# main_board128.net
KiCad netlist of a schematic drawn in EAGLE
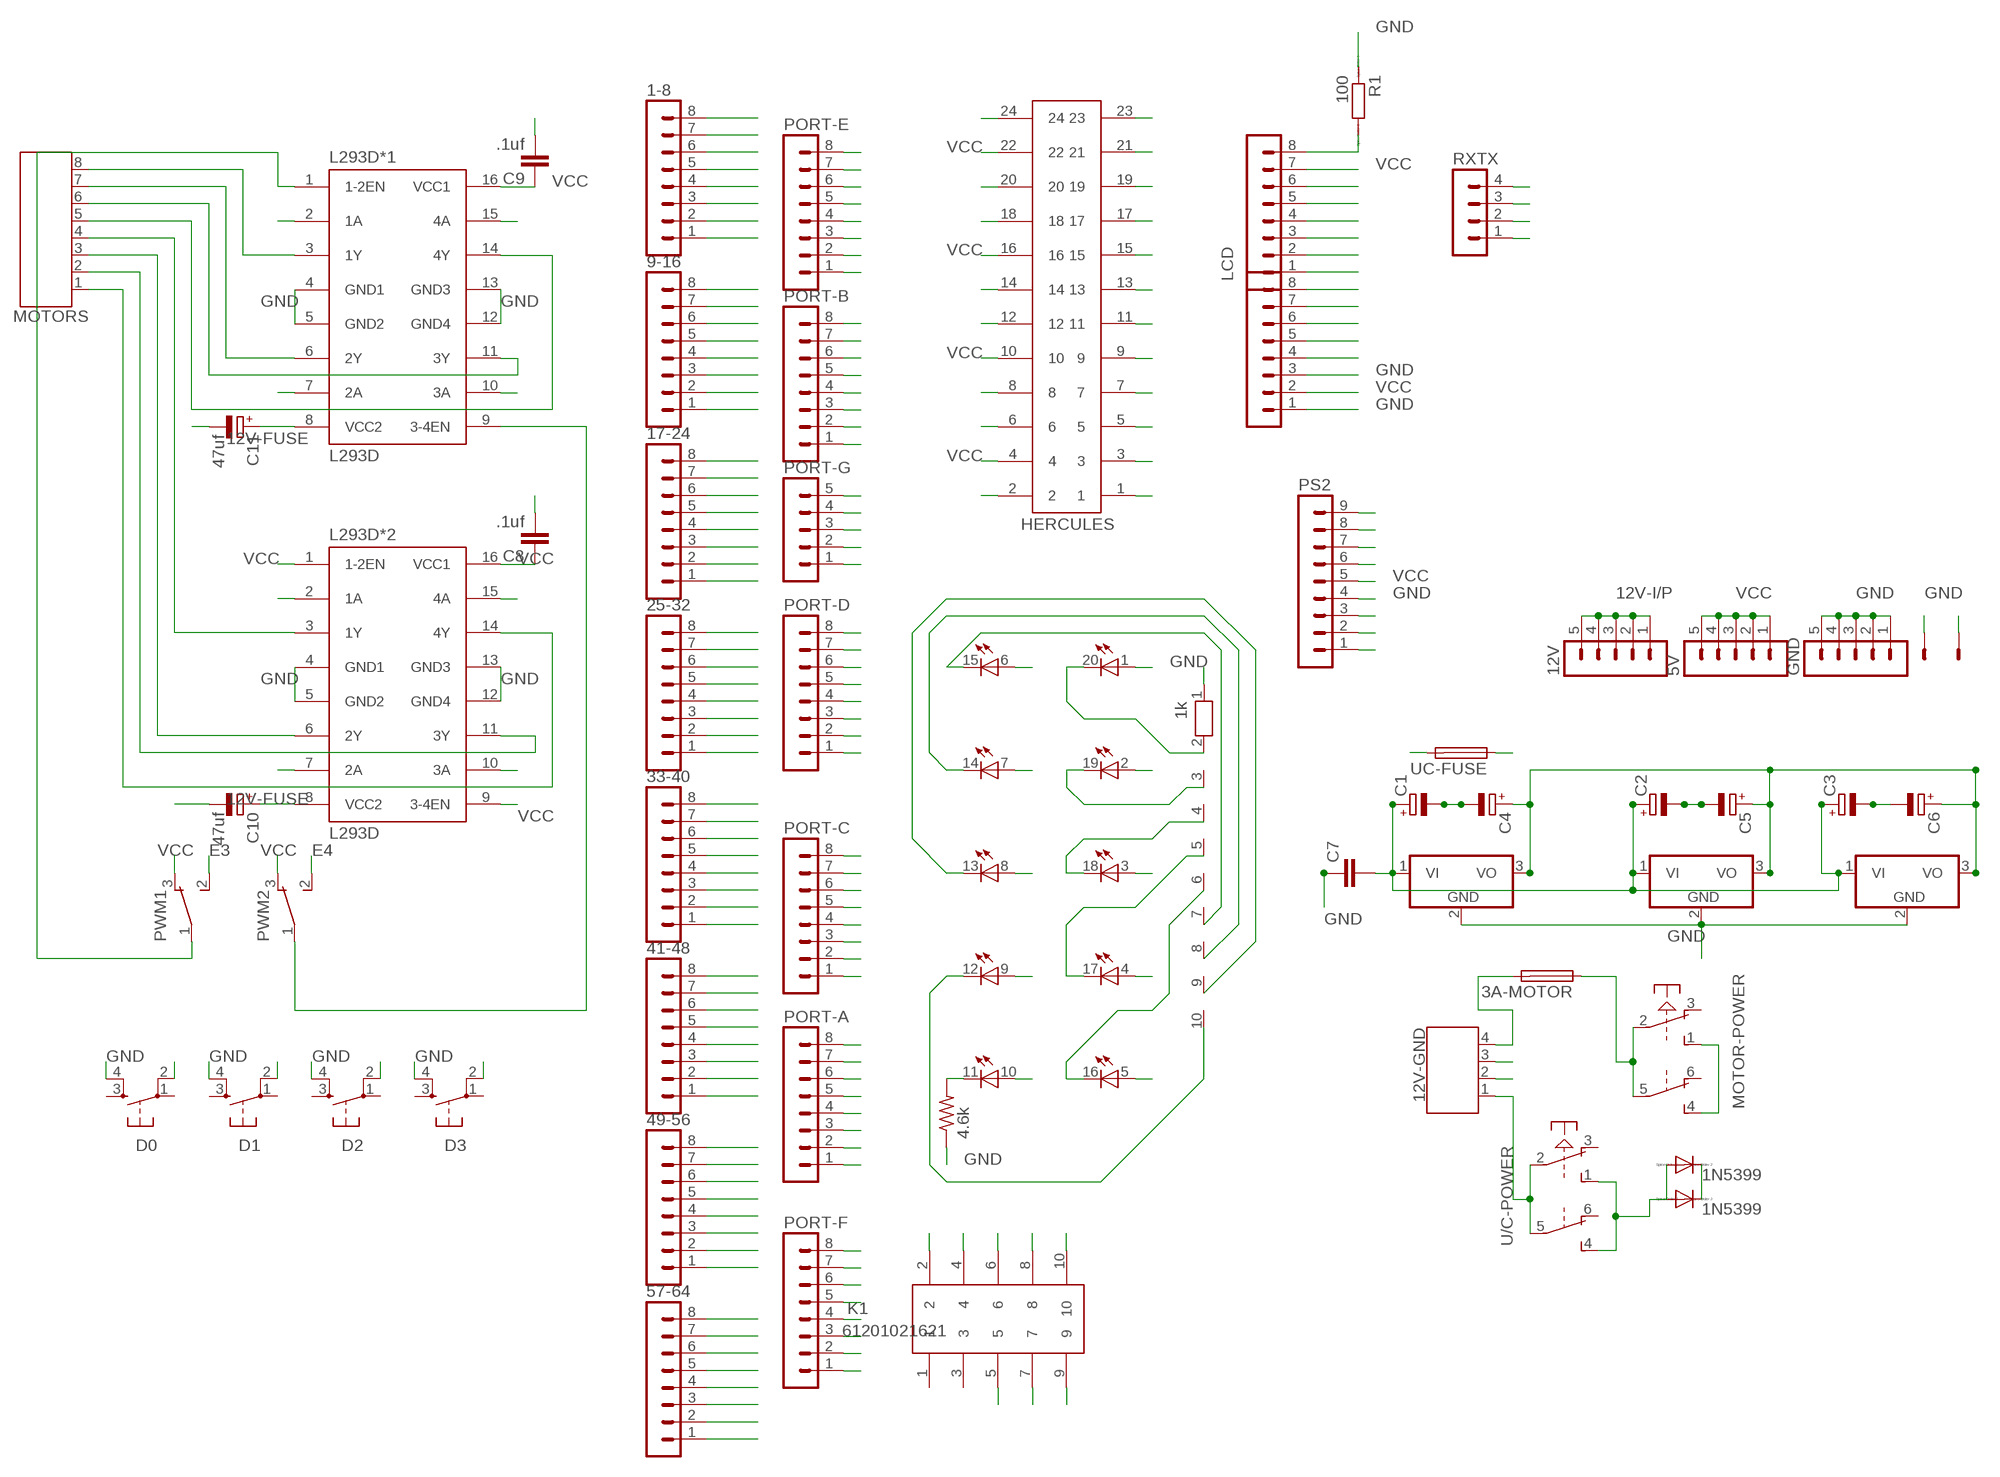
[diagram p0: schematic, sheet 1]

(export (version "E")
  (design (tool "Eeschema 10.0.6"))
  (components
    (comp (ref "1-8")
      (value "MA08-1")
      (footprint "eagle-import:MA08-1")
      (libsource (lib "eagle-import") (part "MA08-1"))
    )
    (comp (ref "3A-MOTOR")
      (value "SH25")
      (footprint "eagle-import:SH25")
      (fields (field (name "MF") "SCHURTER") (field (name "MPN") "0031.8211"))
      (libsource (lib "eagle-import") (part "SH25"))
    )
    (comp (ref "5V")
      (value "MA05-1")
      (footprint "eagle-import:MA05-1")
      (libsource (lib "eagle-import") (part "MA05-1"))
    )
    (comp (ref "9-16")
      (value "MA08-1")
      (footprint "eagle-import:MA08-1")
      (libsource (lib "eagle-import") (part "MA08-1"))
    )
    (comp (ref "12V")
      (value "MA05-1")
      (footprint "eagle-import:MA05-1")
      (libsource (lib "eagle-import") (part "MA05-1"))
    )
    (comp (ref "12V-GND")
      (value "691131710004")
      (footprint "eagle-import:691131710004")
      (libsource (lib "eagle-import") (part "691131710004"))
    )
    (comp (ref "17-24")
      (value "MA08-1")
      (footprint "eagle-import:MA08-1")
      (libsource (lib "eagle-import") (part "MA08-1"))
    )
    (comp (ref "25-32")
      (value "MA08-1")
      (footprint "eagle-import:MA08-1")
      (libsource (lib "eagle-import") (part "MA08-1"))
    )
    (comp (ref "33-40")
      (value "MA08-1")
      (footprint "eagle-import:MA08-1")
      (libsource (lib "eagle-import") (part "MA08-1"))
    )
    (comp (ref "41-48")
      (value "MA08-1")
      (footprint "eagle-import:MA08-1")
      (libsource (lib "eagle-import") (part "MA08-1"))
    )
    (comp (ref "49-56")
      (value "MA08-1")
      (footprint "eagle-import:MA08-1")
      (libsource (lib "eagle-import") (part "MA08-1"))
    )
    (comp (ref "57-64")
      (value "MA08-1")
      (footprint "eagle-import:MA08-1")
      (libsource (lib "eagle-import") (part "MA08-1"))
    )
    (comp (ref "7805-1")
      (value "7805T")
      (footprint "eagle-import:TO220H")
      (libsource (lib "eagle-import") (part "78T05"))
    )
    (comp (ref "7805-2")
      (value "7805T")
      (footprint "eagle-import:TO220H")
      (libsource (lib "eagle-import") (part "78T05"))
    )
    (comp (ref "7805-3")
      (value "7805T")
      (footprint "eagle-import:TO220H")
      (libsource (lib "eagle-import") (part "78T05"))
    )
    (comp (ref "BASEMOTORSLED")
      (value "LB10")
      (footprint "eagle-import:LB10")
      (libsource (lib "eagle-import") (part "LB10"))
    )
    (comp (ref "C1")
      (value "CPOL-EUE2.5-5")
      (footprint "eagle-import:E2,5-5")
      (libsource (lib "eagle-import") (part "CPOL-EUE2.5-5"))
    )
    (comp (ref "C2")
      (value "CPOL-EUE2.5-5")
      (footprint "eagle-import:E2,5-5")
      (libsource (lib "eagle-import") (part "CPOL-EUE2.5-5"))
    )
    (comp (ref "C3")
      (value "CPOL-EUE2.5-5")
      (footprint "eagle-import:E2,5-5")
      (libsource (lib "eagle-import") (part "CPOL-EUE2.5-5"))
    )
    (comp (ref "C4")
      (value "CPOL-EUE2.5-5")
      (footprint "eagle-import:E2,5-5")
      (libsource (lib "eagle-import") (part "CPOL-EUE2.5-5"))
    )
    (comp (ref "C5")
      (value "CPOL-EUE2.5-5")
      (footprint "eagle-import:E2,5-5")
      (libsource (lib "eagle-import") (part "CPOL-EUE2.5-5"))
    )
    (comp (ref "C6")
      (value "CPOL-EUE2.5-5")
      (footprint "eagle-import:E2,5-5")
      (libsource (lib "eagle-import") (part "CPOL-EUE2.5-5"))
    )
    (comp (ref "C7")
      (value "C5/2.5")
      (footprint "eagle-import:C5B2.5")
      (libsource (lib "eagle-import") (part "C5/2.5"))
    )
    (comp (ref "C8")
      (value ".1uf")
      (footprint "eagle-import:C5B2.5")
      (libsource (lib "eagle-import") (part "C5/2.5"))
    )
    (comp (ref "C9")
      (value ".1uf")
      (footprint "eagle-import:C5B2.5")
      (libsource (lib "eagle-import") (part "C5/2.5"))
    )
    (comp (ref "C10")
      (value "47uf")
      (footprint "eagle-import:E2,5-5")
      (libsource (lib "eagle-import") (part "CPOL-EUE2.5-5"))
    )
    (comp (ref "C11")
      (value "47uf")
      (footprint "eagle-import:E2,5-5")
      (libsource (lib "eagle-import") (part "CPOL-EUE2.5-5"))
    )
    (comp (ref "D0")
      (value "DTS-6")
      (footprint "eagle-import:DTS-6")
      (libsource (lib "eagle-import") (part "DTS-6"))
    )
    (comp (ref "D1")
      (value "DTS-6")
      (footprint "eagle-import:DTS-6")
      (libsource (lib "eagle-import") (part "DTS-6"))
    )
    (comp (ref "D2")
      (value "DTS-6")
      (footprint "eagle-import:DTS-6")
      (libsource (lib "eagle-import") (part "DTS-6"))
    )
    (comp (ref "D3")
      (value "DTS-6")
      (footprint "eagle-import:DTS-6")
      (libsource (lib "eagle-import") (part "DTS-6"))
    )
    (comp (ref "GND")
      (value "MA05-1")
      (footprint "eagle-import:MA05-1")
      (libsource (lib "eagle-import") (part "MA05-1"))
    )
    (comp (ref "HERCULES")
      (value "61202421621")
      (footprint "eagle-import:61202421621")
      (libsource (lib "eagle-import") (part "61202421621"))
    )
    (comp (ref "K1")
      (value "61201021621")
      (footprint "eagle-import:61201021621")
      (libsource (lib "eagle-import") (part "61201021621"))
    )
    (comp (ref "L293D*1")
      (value "L293D")
      (footprint "eagle-import:DIL16")
      (libsource (lib "eagle-import") (part "L293D"))
    )
    (comp (ref "L293D*2")
      (value "L293D")
      (footprint "eagle-import:DIL16")
      (libsource (lib "eagle-import") (part "L293D"))
    )
    (comp (ref "LCD")
      (value "MA08-1")
      (footprint "eagle-import:MA08-1")
      (libsource (lib "eagle-import") (part "MA08-1"))
    )
    (comp (ref "LCD*")
      (value "MA08-1")
      (footprint "eagle-import:MA08-1")
      (libsource (lib "eagle-import") (part "MA08-1"))
    )
    (comp (ref "MOTOR-POWER")
      (value "PVA2R")
      (footprint "eagle-import:PVA2R")
      (libsource (lib "eagle-import") (part "PVA2R"))
    )
    (comp (ref "MOTORS")
      (value "691131710008")
      (footprint "eagle-import:691131710008")
      (libsource (lib "eagle-import") (part "691131710008"))
    )
    (comp (ref "PORT-A")
      (value "MA08-1")
      (footprint "eagle-import:MA08-1")
      (libsource (lib "eagle-import") (part "MA08-1"))
    )
    (comp (ref "PORT-B")
      (value "MA08-1")
      (footprint "eagle-import:MA08-1")
      (libsource (lib "eagle-import") (part "MA08-1"))
    )
    (comp (ref "PORT-C")
      (value "MA08-1")
      (footprint "eagle-import:MA08-1")
      (libsource (lib "eagle-import") (part "MA08-1"))
    )
    (comp (ref "PORT-D")
      (value "MA08-1")
      (footprint "eagle-import:MA08-1")
      (libsource (lib "eagle-import") (part "MA08-1"))
    )
    (comp (ref "PORT-E")
      (value "MA08-1")
      (footprint "eagle-import:MA08-1")
      (libsource (lib "eagle-import") (part "MA08-1"))
    )
    (comp (ref "PORT-F")
      (value "MA08-1")
      (footprint "eagle-import:MA08-1")
      (libsource (lib "eagle-import") (part "MA08-1"))
    )
    (comp (ref "PORT-G")
      (value "MA05-1")
      (footprint "eagle-import:MA05-1")
      (libsource (lib "eagle-import") (part "MA05-1"))
    )
    (comp (ref "POWER-D1")
      (value "1N5399")
      (footprint "eagle-import:DO15-12")
      (libsource (lib "eagle-import") (part "1N5060GP"))
    )
    (comp (ref "POWER-D2")
      (value "1N5399")
      (footprint "eagle-import:DO15-12")
      (libsource (lib "eagle-import") (part "1N5060GP"))
    )
    (comp (ref "PS2")
      (value "MA09-1")
      (footprint "eagle-import:MA09-1")
      (libsource (lib "eagle-import") (part "MA09-1"))
    )
    (comp (ref "PWM1")
      (value "450301014042")
      (footprint "eagle-import:450301014042")
      (libsource (lib "eagle-import") (part "450301014042"))
    )
    (comp (ref "PWM2")
      (value "450301014042")
      (footprint "eagle-import:450301014042")
      (libsource (lib "eagle-import") (part "450301014042"))
    )
    (comp (ref "R1")
      (value "100")
      (footprint "eagle-import:0204_7")
      (libsource (lib "eagle-import") (part "R0204/7"))
    )
    (comp (ref "R2")
      (value "4.6k")
      (footprint "eagle-import:0204_5")
      (libsource (lib "eagle-import") (part "R-US_0204/5"))
    )
    (comp (ref "RN1")
      (value "1k")
      (footprint "eagle-import:RN-10")
      (libsource (lib "eagle-import") (part "RN09"))
    )
    (comp (ref "RXTX")
      (value "MA04-1")
      (footprint "eagle-import:MA04-1")
      (libsource (lib "eagle-import") (part "MA04-1"))
    )
    (comp (ref "SENSOR-POWER")
      (value "KK-156-2")
      (footprint "eagle-import:KK-156-2")
      (libsource (lib "eagle-import") (part "KK-156-2"))
    )
    (comp (ref "U/C-POWER")
      (value "PVA2R")
      (footprint "eagle-import:PVA2R")
      (libsource (lib "eagle-import") (part "PVA2R"))
    )
    (comp (ref "UC-FUSE")
      (value "SH25")
      (footprint "eagle-import:SH25")
      (fields (field (name "MF") "SCHURTER") (field (name "MPN") "0031.8211"))
      (libsource (lib "eagle-import") (part "SH25"))
    )
  )
  (nets
    (net (code "1") (name "/12V") (class "Default")
      (node (ref "7805-1") (pin "1") (pinfunction "VI_1") (pintype "input"))
      (node (ref "7805-2") (pin "1") (pinfunction "VI_1") (pintype "input"))
      (node (ref "7805-3") (pin "1") (pinfunction "VI_1") (pintype "input"))
      (node (ref "BASEMOTORSLED") (pin "10") (pinfunction "A_10") (pintype "passive"))
      (node (ref "C1") (pin "+") (pinfunction "+_+") (pintype "passive"))
      (node (ref "C2") (pin "+") (pinfunction "+_+") (pintype "passive"))
      (node (ref "C3") (pin "+") (pinfunction "+_+") (pintype "passive"))
      (node (ref "C7") (pin "2") (pinfunction "2_2") (pintype "passive"))
      (node (ref "POWER-D1") (pin "C") (pinfunction "C_C") (pintype "passive"))
      (node (ref "POWER-D2") (pin "C") (pinfunction "C_C") (pintype "passive"))
    )
    (net (code "2") (name "/12V-FUSE") (class "Default")
      (node (ref "C10") (pin "+") (pinfunction "+_+") (pintype "passive"))
      (node (ref "C11") (pin "+") (pinfunction "+_+") (pintype "passive"))
      (node (ref "L293D*1") (pin "8") (pinfunction "VCC2_8") (pintype "power_in"))
      (node (ref "L293D*2") (pin "8") (pinfunction "VCC2_8") (pintype "power_in"))
      (node (ref "MOTOR-POWER") (pin "1") (pinfunction "S_1") (pintype "passive"))
      (node (ref "MOTOR-POWER") (pin "4") (pinfunction "S_4") (pintype "passive"))
    )
    (net (code "3") (name "/12V-I{slash}P") (class "Default")
      (node (ref "12V") (pin "1") (pinfunction "1_1") (pintype "passive"))
      (node (ref "12V") (pin "2") (pinfunction "2_2") (pintype "passive"))
      (node (ref "12V") (pin "3") (pinfunction "3_3") (pintype "passive"))
      (node (ref "12V") (pin "4") (pinfunction "4_4") (pintype "passive"))
      (node (ref "12V") (pin "5") (pinfunction "5_5") (pintype "passive"))
      (node (ref "12V-GND") (pin "1") (pinfunction "1_1") (pintype "passive"))
      (node (ref "12V-GND") (pin "4") (pinfunction "4_4") (pintype "passive"))
      (node (ref "3A-MOTOR") (pin "2") (pinfunction "2_2") (pintype "passive"))
      (node (ref "U/C-POWER") (pin "2") (pinfunction "P_2") (pintype "passive"))
      (node (ref "U/C-POWER") (pin "5") (pinfunction "P_5") (pintype "passive"))
    )
    (net (code "4") (name "/A0") (class "Default")
      (node (ref "49-56") (pin "3") (pinfunction "3_3") (pintype "passive"))
      (node (ref "LCD") (pin "3") (pinfunction "3_3") (pintype "passive"))
      (node (ref "PORT-A") (pin "1") (pinfunction "1_1") (pintype "passive"))
    )
    (net (code "5") (name "/A1") (class "Default")
      (node (ref "49-56") (pin "2") (pinfunction "2_2") (pintype "passive"))
      (node (ref "LCD") (pin "4") (pinfunction "4_4") (pintype "passive"))
      (node (ref "PORT-A") (pin "2") (pinfunction "2_2") (pintype "passive"))
    )
    (net (code "6") (name "/A2") (class "Default")
      (node (ref "49-56") (pin "1") (pinfunction "1_1") (pintype "passive"))
      (node (ref "LCD") (pin "5") (pinfunction "5_5") (pintype "passive"))
      (node (ref "PORT-A") (pin "3") (pinfunction "3_3") (pintype "passive"))
    )
    (net (code "7") (name "/A3") (class "Default")
      (node (ref "41-48") (pin "8") (pinfunction "8_8") (pintype "passive"))
      (node (ref "LCD") (pin "6") (pinfunction "6_6") (pintype "passive"))
      (node (ref "PORT-A") (pin "4") (pinfunction "4_4") (pintype "passive"))
    )
    (net (code "8") (name "/A4") (class "Default")
      (node (ref "41-48") (pin "7") (pinfunction "7_7") (pintype "passive"))
      (node (ref "PORT-A") (pin "5") (pinfunction "5_5") (pintype "passive"))
    )
    (net (code "9") (name "/A5") (class "Default")
      (node (ref "41-48") (pin "6") (pinfunction "6_6") (pintype "passive"))
      (node (ref "LCD*") (pin "4") (pinfunction "4_4") (pintype "passive"))
      (node (ref "PORT-A") (pin "6") (pinfunction "6_6") (pintype "passive"))
    )
    (net (code "10") (name "/A6") (class "Default")
      (node (ref "41-48") (pin "5") (pinfunction "5_5") (pintype "passive"))
      (node (ref "LCD*") (pin "5") (pinfunction "5_5") (pintype "passive"))
      (node (ref "PORT-A") (pin "7") (pinfunction "7_7") (pintype "passive"))
    )
    (net (code "11") (name "/A7") (class "Default")
      (node (ref "41-48") (pin "4") (pinfunction "4_4") (pintype "passive"))
      (node (ref "LCD*") (pin "6") (pinfunction "6_6") (pintype "passive"))
      (node (ref "PORT-A") (pin "8") (pinfunction "8_8") (pintype "passive"))
    )
    (net (code "12") (name "/B0") (class "Default")
      (node (ref "9-16") (pin "2") (pinfunction "2_2") (pintype "passive"))
      (node (ref "L293D*2") (pin "2") (pinfunction "1A_2") (pintype "input"))
      (node (ref "PORT-B") (pin "1") (pinfunction "1_1") (pintype "passive"))
    )
    (net (code "13") (name "/B1") (class "Default")
      (node (ref "9-16") (pin "3") (pinfunction "3_3") (pintype "passive"))
      (node (ref "L293D*2") (pin "7") (pinfunction "2A_7") (pintype "input"))
      (node (ref "PORT-B") (pin "2") (pinfunction "2_2") (pintype "passive"))
    )
    (net (code "14") (name "/B2") (class "Default")
      (node (ref "9-16") (pin "4") (pinfunction "4_4") (pintype "passive"))
      (node (ref "L293D*2") (pin "10") (pinfunction "3A_10") (pintype "input"))
      (node (ref "PORT-B") (pin "3") (pinfunction "3_3") (pintype "passive"))
    )
    (net (code "15") (name "/B3") (class "Default")
      (node (ref "9-16") (pin "5") (pinfunction "5_5") (pintype "passive"))
      (node (ref "L293D*2") (pin "15") (pinfunction "4A_15") (pintype "input"))
      (node (ref "PORT-B") (pin "4") (pinfunction "4_4") (pintype "passive"))
    )
    (net (code "16") (name "/B4") (class "Default")
      (node (ref "9-16") (pin "6") (pinfunction "6_6") (pintype "passive"))
      (node (ref "HERCULES") (pin "3") (pinfunction "3_3") (pintype "passive"))
      (node (ref "PORT-B") (pin "5") (pinfunction "5_5") (pintype "passive"))
    )
    (net (code "17") (name "/B5") (class "Default")
      (node (ref "9-16") (pin "7") (pinfunction "7_7") (pintype "passive"))
      (node (ref "HERCULES") (pin "9") (pinfunction "9_9") (pintype "passive"))
      (node (ref "PORT-B") (pin "6") (pinfunction "6_6") (pintype "passive"))
    )
    (net (code "18") (name "/B6") (class "Default")
      (node (ref "9-16") (pin "8") (pinfunction "8_8") (pintype "passive"))
      (node (ref "HERCULES") (pin "15") (pinfunction "15_15") (pintype "passive"))
      (node (ref "PORT-B") (pin "7") (pinfunction "7_7") (pintype "passive"))
    )
    (net (code "19") (name "/B7") (class "Default")
      (node (ref "17-24") (pin "1") (pinfunction "1_1") (pintype "passive"))
      (node (ref "HERCULES") (pin "21") (pinfunction "21_21") (pintype "passive"))
      (node (ref "PORT-B") (pin "8") (pinfunction "8_8") (pintype "passive"))
    )
    (net (code "20") (name "/C0") (class "Default")
      (node (ref "33-40") (pin "3") (pinfunction "3_3") (pintype "passive"))
      (node (ref "BASEMOTORSLED") (pin "1") (pinfunction "A_1") (pintype "passive"))
      (node (ref "HERCULES") (pin "1") (pinfunction "1_1") (pintype "passive"))
      (node (ref "PORT-C") (pin "1") (pinfunction "1_1") (pintype "passive"))
    )
    (net (code "21") (name "/C1") (class "Default")
      (node (ref "33-40") (pin "4") (pinfunction "4_4") (pintype "passive"))
      (node (ref "BASEMOTORSLED") (pin "2") (pinfunction "A_2") (pintype "passive"))
      (node (ref "HERCULES") (pin "5") (pinfunction "5_5") (pintype "passive"))
      (node (ref "PORT-C") (pin "2") (pinfunction "2_2") (pintype "passive"))
    )
    (net (code "22") (name "/C2") (class "Default")
      (node (ref "33-40") (pin "5") (pinfunction "5_5") (pintype "passive"))
      (node (ref "BASEMOTORSLED") (pin "3") (pinfunction "A_3") (pintype "passive"))
      (node (ref "HERCULES") (pin "7") (pinfunction "7_7") (pintype "passive"))
      (node (ref "PORT-C") (pin "3") (pinfunction "3_3") (pintype "passive"))
    )
    (net (code "23") (name "/C3") (class "Default")
      (node (ref "33-40") (pin "6") (pinfunction "6_6") (pintype "passive"))
      (node (ref "BASEMOTORSLED") (pin "4") (pinfunction "A_4") (pintype "passive"))
      (node (ref "HERCULES") (pin "11") (pinfunction "11_11") (pintype "passive"))
      (node (ref "PORT-C") (pin "4") (pinfunction "4_4") (pintype "passive"))
    )
    (net (code "24") (name "/C4") (class "Default")
      (node (ref "33-40") (pin "7") (pinfunction "7_7") (pintype "passive"))
      (node (ref "BASEMOTORSLED") (pin "5") (pinfunction "A_5") (pintype "passive"))
      (node (ref "HERCULES") (pin "13") (pinfunction "13_13") (pintype "passive"))
      (node (ref "PORT-C") (pin "5") (pinfunction "5_5") (pintype "passive"))
    )
    (net (code "25") (name "/C5") (class "Default")
      (node (ref "33-40") (pin "8") (pinfunction "8_8") (pintype "passive"))
      (node (ref "BASEMOTORSLED") (pin "6") (pinfunction "A_6") (pintype "passive"))
      (node (ref "HERCULES") (pin "17") (pinfunction "17_17") (pintype "passive"))
      (node (ref "PORT-C") (pin "6") (pinfunction "6_6") (pintype "passive"))
    )
    (net (code "26") (name "/C6") (class "Default")
      (node (ref "41-48") (pin "1") (pinfunction "1_1") (pintype "passive"))
      (node (ref "BASEMOTORSLED") (pin "7") (pinfunction "A_7") (pintype "passive"))
      (node (ref "HERCULES") (pin "19") (pinfunction "19_19") (pintype "passive"))
      (node (ref "PORT-C") (pin "7") (pinfunction "7_7") (pintype "passive"))
    )
    (net (code "27") (name "/C7") (class "Default")
      (node (ref "41-48") (pin "2") (pinfunction "2_2") (pintype "passive"))
      (node (ref "BASEMOTORSLED") (pin "8") (pinfunction "A_8") (pintype "passive"))
      (node (ref "HERCULES") (pin "23") (pinfunction "23_23") (pintype "passive"))
      (node (ref "PORT-C") (pin "8") (pinfunction "8_8") (pintype "passive"))
    )
    (net (code "28") (name "/D0") (class "Default")
      (node (ref "25-32") (pin "1") (pinfunction "1_1") (pintype "passive"))
      (node (ref "D0") (pin "2") (pinfunction "2_2") (pintype "passive"))
      (node (ref "HERCULES") (pin "2") (pinfunction "2_2") (pintype "passive"))
      (node (ref "PORT-D") (pin "1") (pinfunction "1_1") (pintype "passive"))
    )
    (net (code "29") (name "/D1") (class "Default")
      (node (ref "25-32") (pin "2") (pinfunction "2_2") (pintype "passive"))
      (node (ref "D1") (pin "2") (pinfunction "2_2") (pintype "passive"))
      (node (ref "HERCULES") (pin "6") (pinfunction "6_6") (pintype "passive"))
      (node (ref "PORT-D") (pin "2") (pinfunction "2_2") (pintype "passive"))
    )
    (net (code "30") (name "/D2") (class "Default")
      (node (ref "25-32") (pin "3") (pinfunction "3_3") (pintype "passive"))
      (node (ref "D2") (pin "2") (pinfunction "2_2") (pintype "passive"))
      (node (ref "HERCULES") (pin "8") (pinfunction "8_8") (pintype "passive"))
      (node (ref "PORT-D") (pin "3") (pinfunction "3_3") (pintype "passive"))
      (node (ref "RXTX") (pin "3") (pinfunction "3_3") (pintype "passive"))
    )
    (net (code "31") (name "/D3") (class "Default")
      (node (ref "25-32") (pin "4") (pinfunction "4_4") (pintype "passive"))
      (node (ref "D3") (pin "2") (pinfunction "2_2") (pintype "passive"))
      (node (ref "HERCULES") (pin "12") (pinfunction "12_12") (pintype "passive"))
      (node (ref "PORT-D") (pin "4") (pinfunction "4_4") (pintype "passive"))
      (node (ref "RXTX") (pin "4") (pinfunction "4_4") (pintype "passive"))
    )
    (net (code "32") (name "/D4") (class "Default")
      (node (ref "25-32") (pin "5") (pinfunction "5_5") (pintype "passive"))
      (node (ref "HERCULES") (pin "14") (pinfunction "14_14") (pintype "passive"))
      (node (ref "PORT-D") (pin "5") (pinfunction "5_5") (pintype "passive"))
    )
    (net (code "33") (name "/D5") (class "Default")
      (node (ref "25-32") (pin "6") (pinfunction "6_6") (pintype "passive"))
      (node (ref "HERCULES") (pin "18") (pinfunction "18_18") (pintype "passive"))
      (node (ref "PORT-D") (pin "6") (pinfunction "6_6") (pintype "passive"))
    )
    (net (code "34") (name "/D6") (class "Default")
      (node (ref "25-32") (pin "7") (pinfunction "7_7") (pintype "passive"))
      (node (ref "HERCULES") (pin "20") (pinfunction "20_20") (pintype "passive"))
      (node (ref "PORT-D") (pin "7") (pinfunction "7_7") (pintype "passive"))
    )
    (net (code "35") (name "/D7") (class "Default")
      (node (ref "25-32") (pin "8") (pinfunction "8_8") (pintype "passive"))
      (node (ref "HERCULES") (pin "24") (pinfunction "24_24") (pintype "passive"))
      (node (ref "PORT-D") (pin "8") (pinfunction "8_8") (pintype "passive"))
    )
    (net (code "36") (name "/E0") (class "Default")
      (node (ref "1-8") (pin "2") (pinfunction "2_2") (pintype "passive"))
      (node (ref "L293D*1") (pin "2") (pinfunction "1A_2") (pintype "input"))
      (node (ref "PORT-E") (pin "1") (pinfunction "1_1") (pintype "passive"))
      (node (ref "RXTX") (pin "1") (pinfunction "1_1") (pintype "passive"))
    )
    (net (code "37") (name "/E1") (class "Default")
      (node (ref "1-8") (pin "3") (pinfunction "3_3") (pintype "passive"))
      (node (ref "L293D*1") (pin "7") (pinfunction "2A_7") (pintype "input"))
      (node (ref "PORT-E") (pin "2") (pinfunction "2_2") (pintype "passive"))
      (node (ref "RXTX") (pin "2") (pinfunction "2_2") (pintype "passive"))
    )
    (net (code "38") (name "/E2") (class "Default")
      (node (ref "1-8") (pin "4") (pinfunction "4_4") (pintype "passive"))
      (node (ref "PORT-E") (pin "3") (pinfunction "3_3") (pintype "passive"))
    )
    (net (code "39") (name "/E3") (class "Default")
      (node (ref "1-8") (pin "5") (pinfunction "5_5") (pintype "passive"))
      (node (ref "PORT-E") (pin "4") (pinfunction "4_4") (pintype "passive"))
      (node (ref "PWM1") (pin "2") (pinfunction "2_2") (pintype "passive"))
    )
    (net (code "40") (name "/E4") (class "Default")
      (node (ref "1-8") (pin "6") (pinfunction "6_6") (pintype "passive"))
      (node (ref "PORT-E") (pin "5") (pinfunction "5_5") (pintype "passive"))
      (node (ref "PWM2") (pin "2") (pinfunction "2_2") (pintype "passive"))
    )
    (net (code "41") (name "/E5") (class "Default")
      (node (ref "1-8") (pin "7") (pinfunction "7_7") (pintype "passive"))
      (node (ref "PORT-E") (pin "6") (pinfunction "6_6") (pintype "passive"))
    )
    (net (code "42") (name "/E6") (class "Default")
      (node (ref "1-8") (pin "8") (pinfunction "8_8") (pintype "passive"))
      (node (ref "L293D*1") (pin "10") (pinfunction "3A_10") (pintype "input"))
      (node (ref "PORT-E") (pin "7") (pinfunction "7_7") (pintype "passive"))
    )
    (net (code "43") (name "/E7") (class "Default")
      (node (ref "9-16") (pin "1") (pinfunction "1_1") (pintype "passive"))
      (node (ref "L293D*1") (pin "15") (pinfunction "4A_15") (pintype "input"))
      (node (ref "PORT-E") (pin "8") (pinfunction "8_8") (pintype "passive"))
    )
    (net (code "44") (name "/F0") (class "Default")
      (node (ref "57-64") (pin "5") (pinfunction "5_5") (pintype "passive"))
      (node (ref "K1") (pin "2") (pinfunction "2_2") (pintype "passive"))
      (node (ref "PORT-F") (pin "1") (pinfunction "1_1") (pintype "passive"))
    )
    (net (code "45") (name "/F1") (class "Default")
      (node (ref "57-64") (pin "4") (pinfunction "4_4") (pintype "passive"))
      (node (ref "K1") (pin "4") (pinfunction "4_4") (pintype "passive"))
      (node (ref "PORT-F") (pin "2") (pinfunction "2_2") (pintype "passive"))
    )
    (net (code "46") (name "/F2") (class "Default")
      (node (ref "57-64") (pin "3") (pinfunction "3_3") (pintype "passive"))
      (node (ref "K1") (pin "6") (pinfunction "6_6") (pintype "passive"))
      (node (ref "PORT-F") (pin "3") (pinfunction "3_3") (pintype "passive"))
    )
    (net (code "47") (name "/F3") (class "Default")
      (node (ref "57-64") (pin "2") (pinfunction "2_2") (pintype "passive"))
      (node (ref "K1") (pin "8") (pinfunction "8_8") (pintype "passive"))
      (node (ref "PORT-F") (pin "4") (pinfunction "4_4") (pintype "passive"))
    )
    (net (code "48") (name "/F4") (class "Default")
      (node (ref "57-64") (pin "1") (pinfunction "1_1") (pintype "passive"))
      (node (ref "K1") (pin "10") (pinfunction "10_10") (pintype "passive"))
      (node (ref "PORT-F") (pin "5") (pinfunction "5_5") (pintype "passive"))
    )
    (net (code "49") (name "/F5") (class "Default")
      (node (ref "49-56") (pin "8") (pinfunction "8_8") (pintype "passive"))
      (node (ref "K1") (pin "9") (pinfunction "9_9") (pintype "passive"))
      (node (ref "PORT-F") (pin "6") (pinfunction "6_6") (pintype "passive"))
    )
    (net (code "50") (name "/F6") (class "Default")
      (node (ref "49-56") (pin "7") (pinfunction "7_7") (pintype "passive"))
      (node (ref "K1") (pin "7") (pinfunction "7_7") (pintype "passive"))
      (node (ref "PORT-F") (pin "7") (pinfunction "7_7") (pintype "passive"))
    )
    (net (code "51") (name "/F7") (class "Default")
      (node (ref "49-56") (pin "6") (pinfunction "6_6") (pintype "passive"))
      (node (ref "K1") (pin "5") (pinfunction "5_5") (pintype "passive"))
      (node (ref "PORT-F") (pin "8") (pinfunction "8_8") (pintype "passive"))
    )
    (net (code "52") (name "/FUSE-M{slash}C") (class "Default")
      (node (ref "7805-1") (pin "3") (pinfunction "VO_3") (pintype "passive"))
      (node (ref "7805-2") (pin "3") (pinfunction "VO_3") (pintype "passive"))
      (node (ref "7805-3") (pin "3") (pinfunction "VO_3") (pintype "passive"))
      (node (ref "C4") (pin "+") (pinfunction "+_+") (pintype "passive"))
      (node (ref "C5") (pin "+") (pinfunction "+_+") (pintype "passive"))
      (node (ref "C6") (pin "+") (pinfunction "+_+") (pintype "passive"))
      (node (ref "UC-FUSE") (pin "1") (pinfunction "1_1") (pintype "passive"))
    )
    (net (code "53") (name "/G0") (class "Default")
      (node (ref "33-40") (pin "1") (pinfunction "1_1") (pintype "passive"))
      (node (ref "PORT-G") (pin "1") (pinfunction "1_1") (pintype "passive"))
      (node (ref "PS2") (pin "1") (pinfunction "1_1") (pintype "passive"))
    )
    (net (code "54") (name "/G1") (class "Default")
      (node (ref "33-40") (pin "2") (pinfunction "2_2") (pintype "passive"))
      (node (ref "PORT-G") (pin "2") (pinfunction "2_2") (pintype "passive"))
      (node (ref "PS2") (pin "2") (pinfunction "2_2") (pintype "passive"))
    )
    (net (code "55") (name "/G2") (class "Default")
      (node (ref "41-48") (pin "3") (pinfunction "3_3") (pintype "passive"))
      (node (ref "PORT-G") (pin "3") (pinfunction "3_3") (pintype "passive"))
      (node (ref "PS2") (pin "6") (pinfunction "6_6") (pintype "passive"))
    )
    (net (code "56") (name "/G3") (class "Default")
      (node (ref "17-24") (pin "2") (pinfunction "2_2") (pintype "passive"))
      (node (ref "PORT-G") (pin "4") (pinfunction "4_4") (pintype "passive"))
      (node (ref "PS2") (pin "7") (pinfunction "7_7") (pintype "passive"))
    )
    (net (code "57") (name "/G4") (class "Default")
      (node (ref "17-24") (pin "3") (pinfunction "3_3") (pintype "passive"))
      (node (ref "PORT-G") (pin "5") (pinfunction "5_5") (pintype "passive"))
    )
    (net (code "58") (name "/GND") (class "Default")
      (node (ref "12V-GND") (pin "2") (pinfunction "2_2") (pintype "passive"))
      (node (ref "12V-GND") (pin "3") (pinfunction "3_3") (pintype "passive"))
      (node (ref "17-24") (pin "6") (pinfunction "6_6") (pintype "passive"))
      (node (ref "49-56") (pin "5") (pinfunction "5_5") (pintype "passive"))
      (node (ref "57-64") (pin "7") (pinfunction "7_7") (pintype "passive"))
      (node (ref "7805-1") (pin "2") (pinfunction "GND_2") (pintype "passive"))
      (node (ref "7805-2") (pin "2") (pinfunction "GND_2") (pintype "passive"))
      (node (ref "7805-3") (pin "2") (pinfunction "GND_2") (pintype "passive"))
      (node (ref "C1") (pin "-") (pinfunction "-_-") (pintype "passive"))
      (node (ref "C10") (pin "-") (pinfunction "-_-") (pintype "passive"))
      (node (ref "C11") (pin "-") (pinfunction "-_-") (pintype "passive"))
      (node (ref "C2") (pin "-") (pinfunction "-_-") (pintype "passive"))
      (node (ref "C3") (pin "-") (pinfunction "-_-") (pintype "passive"))
      (node (ref "C4") (pin "-") (pinfunction "-_-") (pintype "passive"))
      (node (ref "C5") (pin "-") (pinfunction "-_-") (pintype "passive"))
      (node (ref "C6") (pin "-") (pinfunction "-_-") (pintype "passive"))
      (node (ref "C7") (pin "1") (pinfunction "1_1") (pintype "passive"))
      (node (ref "C8") (pin "2") (pinfunction "2_2") (pintype "passive"))
      (node (ref "C9") (pin "2") (pinfunction "2_2") (pintype "passive"))
      (node (ref "D0") (pin "4") (pinfunction "4_4") (pintype "passive"))
      (node (ref "D1") (pin "4") (pinfunction "4_4") (pintype "passive"))
      (node (ref "D2") (pin "4") (pinfunction "4_4") (pintype "passive"))
      (node (ref "D3") (pin "4") (pinfunction "4_4") (pintype "passive"))
      (node (ref "GND") (pin "1") (pinfunction "1_1") (pintype "passive"))
      (node (ref "GND") (pin "2") (pinfunction "2_2") (pintype "passive"))
      (node (ref "GND") (pin "3") (pinfunction "3_3") (pintype "passive"))
      (node (ref "GND") (pin "4") (pinfunction "4_4") (pintype "passive"))
      (node (ref "GND") (pin "5") (pinfunction "5_5") (pintype "passive"))
      (node (ref "L293D*1") (pin "12") (pinfunction "GND4_12") (pintype "power_in"))
      (node (ref "L293D*1") (pin "13") (pinfunction "GND3_13") (pintype "power_in"))
      (node (ref "L293D*1") (pin "4") (pinfunction "GND1_4") (pintype "power_in"))
      (node (ref "L293D*1") (pin "5") (pinfunction "GND2_5") (pintype "power_in"))
      (node (ref "L293D*2") (pin "12") (pinfunction "GND4_12") (pintype "power_in"))
      (node (ref "L293D*2") (pin "13") (pinfunction "GND3_13") (pintype "power_in"))
      (node (ref "L293D*2") (pin "4") (pinfunction "GND1_4") (pintype "power_in"))
      (node (ref "L293D*2") (pin "5") (pinfunction "GND2_5") (pintype "power_in"))
      (node (ref "LCD*") (pin "1") (pinfunction "1_1") (pintype "passive"))
      (node (ref "LCD*") (pin "3") (pinfunction "3_3") (pintype "passive"))
      (node (ref "PS2") (pin "4") (pinfunction "4_4") (pintype "passive"))
      (node (ref "R1") (pin "1") (pinfunction "1_1") (pintype "passive"))
      (node (ref "R2") (pin "1") (pinfunction "1_1") (pintype "passive"))
      (node (ref "RN1") (pin "1") (pinfunction "1_1") (pintype "passive"))
      (node (ref "SENSOR-POWER") (pin "2") (pinfunction "S_2") (pintype "passive"))
    )
    (net (code "59") (name "/VCC") (class "Default")
      (node (ref "17-24") (pin "5") (pinfunction "5_5") (pintype "passive"))
      (node (ref "49-56") (pin "4") (pinfunction "4_4") (pintype "passive"))
      (node (ref "57-64") (pin "8") (pinfunction "8_8") (pintype "passive"))
      (node (ref "5V") (pin "1") (pinfunction "1_1") (pintype "passive"))
      (node (ref "5V") (pin "2") (pinfunction "2_2") (pintype "passive"))
      (node (ref "5V") (pin "3") (pinfunction "3_3") (pintype "passive"))
      (node (ref "5V") (pin "4") (pinfunction "4_4") (pintype "passive"))
      (node (ref "5V") (pin "5") (pinfunction "5_5") (pintype "passive"))
      (node (ref "BASEMOTORSLED") (pin "9") (pinfunction "A_9") (pintype "passive"))
      (node (ref "C8") (pin "1") (pinfunction "1_1") (pintype "passive"))
      (node (ref "C9") (pin "1") (pinfunction "1_1") (pintype "passive"))
      (node (ref "HERCULES") (pin "10") (pinfunction "10_10") (pintype "passive"))
      (node (ref "HERCULES") (pin "16") (pinfunction "16_16") (pintype "passive"))
      (node (ref "HERCULES") (pin "22") (pinfunction "22_22") (pintype "passive"))
      (node (ref "HERCULES") (pin "4") (pinfunction "4_4") (pintype "passive"))
      (node (ref "L293D*1") (pin "16") (pinfunction "VCC1_16") (pintype "power_in"))
      (node (ref "L293D*2") (pin "1") (pinfunction "1-2EN_1") (pintype "input"))
      (node (ref "L293D*2") (pin "16") (pinfunction "VCC1_16") (pintype "power_in"))
      (node (ref "L293D*2") (pin "9") (pinfunction "3-4EN_9") (pintype "input"))
      (node (ref "LCD") (pin "7") (pinfunction "7_7") (pintype "passive"))
      (node (ref "LCD*") (pin "2") (pinfunction "2_2") (pintype "passive"))
      (node (ref "PS2") (pin "5") (pinfunction "5_5") (pintype "passive"))
      (node (ref "PWM1") (pin "3") (pinfunction "3_3") (pintype "passive"))
      (node (ref "PWM2") (pin "3") (pinfunction "3_3") (pintype "passive"))
      (node (ref "SENSOR-POWER") (pin "1") (pinfunction "S_1") (pintype "passive"))
      (node (ref "UC-FUSE") (pin "2") (pinfunction "2_2") (pintype "passive"))
    )
    (net (code "60") (name "Net-(BASEMOTORSLEDA-C)") (class "Default")
      (node (ref "BASEMOTORSLED") (pin "20") (pinfunction "C_20") (pintype "passive"))
      (node (ref "RN1") (pin "2") (pinfunction "2_2") (pintype "passive"))
    )
    (net (code "61") (name "Net-(BASEMOTORSLEDB-C)") (class "Default")
      (node (ref "BASEMOTORSLED") (pin "11") (pinfunction "C_11") (pintype "passive"))
      (node (ref "R2") (pin "2") (pinfunction "2_2") (pintype "passive"))
    )
    (net (code "62") (name "Net-(BASEMOTORSLEDC-C)") (class "Default")
      (node (ref "BASEMOTORSLED") (pin "19") (pinfunction "C_19") (pintype "passive"))
      (node (ref "RN1") (pin "3") (pinfunction "3_3") (pintype "passive"))
    )
    (net (code "63") (name "Net-(BASEMOTORSLEDD-C)") (class "Default")
      (node (ref "BASEMOTORSLED") (pin "18") (pinfunction "C_18") (pintype "passive"))
      (node (ref "RN1") (pin "4") (pinfunction "4_4") (pintype "passive"))
    )
    (net (code "64") (name "Net-(BASEMOTORSLEDE-C)") (class "Default")
      (node (ref "BASEMOTORSLED") (pin "17") (pinfunction "C_17") (pintype "passive"))
      (node (ref "RN1") (pin "5") (pinfunction "5_5") (pintype "passive"))
    )
    (net (code "65") (name "Net-(BASEMOTORSLEDF-C)") (class "Default")
      (node (ref "BASEMOTORSLED") (pin "16") (pinfunction "C_16") (pintype "passive"))
      (node (ref "RN1") (pin "6") (pinfunction "6_6") (pintype "passive"))
    )
    (net (code "66") (name "Net-(BASEMOTORSLEDG-C)") (class "Default")
      (node (ref "BASEMOTORSLED") (pin "15") (pinfunction "C_15") (pintype "passive"))
      (node (ref "RN1") (pin "7") (pinfunction "7_7") (pintype "passive"))
    )
    (net (code "67") (name "Net-(BASEMOTORSLEDH-C)") (class "Default")
      (node (ref "BASEMOTORSLED") (pin "14") (pinfunction "C_14") (pintype "passive"))
      (node (ref "RN1") (pin "8") (pinfunction "8_8") (pintype "passive"))
    )
    (net (code "68") (name "Net-(BASEMOTORSLEDI-C)") (class "Default")
      (node (ref "BASEMOTORSLED") (pin "13") (pinfunction "C_13") (pintype "passive"))
      (node (ref "RN1") (pin "9") (pinfunction "9_9") (pintype "passive"))
    )
    (net (code "69") (name "Net-(BASEMOTORSLEDJ-C)") (class "Default")
      (node (ref "BASEMOTORSLED") (pin "12") (pinfunction "C_12") (pintype "passive"))
      (node (ref "RN1") (pin "10") (pinfunction "10_10") (pintype "passive"))
    )
    (net (code "70") (name "Net-(L293D*1-1-2EN)") (class "Default")
      (node (ref "L293D*1") (pin "1") (pinfunction "1-2EN_1") (pintype "input"))
      (node (ref "PWM1") (pin "1") (pinfunction "1_1") (pintype "passive"))
    )
    (net (code "71") (name "Net-(L293D*1-1Y)") (class "Default")
      (node (ref "L293D*1") (pin "3") (pinfunction "1Y_3") (pintype "output"))
      (node (ref "MOTORS") (pin "8") (pinfunction "8_8") (pintype "passive"))
    )
    (net (code "72") (name "Net-(L293D*1-2Y)") (class "Default")
      (node (ref "L293D*1") (pin "6") (pinfunction "2Y_6") (pintype "output"))
      (node (ref "MOTORS") (pin "7") (pinfunction "7_7") (pintype "passive"))
    )
    (net (code "73") (name "Net-(L293D*1-3-4EN)") (class "Default")
      (node (ref "L293D*1") (pin "9") (pinfunction "3-4EN_9") (pintype "input"))
      (node (ref "PWM2") (pin "1") (pinfunction "1_1") (pintype "passive"))
    )
    (net (code "74") (name "Net-(L293D*1-3Y)") (class "Default")
      (node (ref "L293D*1") (pin "11") (pinfunction "3Y_11") (pintype "output"))
      (node (ref "MOTORS") (pin "6") (pinfunction "6_6") (pintype "passive"))
    )
    (net (code "75") (name "Net-(L293D*1-4Y)") (class "Default")
      (node (ref "L293D*1") (pin "14") (pinfunction "4Y_14") (pintype "output"))
      (node (ref "MOTORS") (pin "5") (pinfunction "5_5") (pintype "passive"))
    )
    (net (code "76") (name "Net-(L293D*2-1Y)") (class "Default")
      (node (ref "L293D*2") (pin "3") (pinfunction "1Y_3") (pintype "output"))
      (node (ref "MOTORS") (pin "4") (pinfunction "4_4") (pintype "passive"))
    )
    (net (code "77") (name "Net-(L293D*2-2Y)") (class "Default")
      (node (ref "L293D*2") (pin "6") (pinfunction "2Y_6") (pintype "output"))
      (node (ref "MOTORS") (pin "3") (pinfunction "3_3") (pintype "passive"))
    )
    (net (code "78") (name "Net-(L293D*2-3Y)") (class "Default")
      (node (ref "L293D*2") (pin "11") (pinfunction "3Y_11") (pintype "output"))
      (node (ref "MOTORS") (pin "2") (pinfunction "2_2") (pintype "passive"))
    )
    (net (code "79") (name "Net-(L293D*2-4Y)") (class "Default")
      (node (ref "L293D*2") (pin "14") (pinfunction "4Y_14") (pintype "output"))
      (node (ref "MOTORS") (pin "1") (pinfunction "1_1") (pintype "passive"))
    )
    (net (code "80") (name "Net-(LCD-Pad8)") (class "Default")
      (node (ref "LCD") (pin "8") (pinfunction "8_8") (pintype "passive"))
      (node (ref "R1") (pin "2") (pinfunction "2_2") (pintype "passive"))
    )
    (net (code "81") (name "Net-(MOTOR-POWERA-P)") (class "Default")
      (node (ref "3A-MOTOR") (pin "1") (pinfunction "1_1") (pintype "passive"))
      (node (ref "MOTOR-POWER") (pin "2") (pinfunction "P_2") (pintype "passive"))
      (node (ref "MOTOR-POWER") (pin "5") (pinfunction "P_5") (pintype "passive"))
    )
    (net (code "82") (name "Net-(U/C-POWERA-S)") (class "Default")
      (node (ref "POWER-D1") (pin "A") (pinfunction "A_A") (pintype "passive"))
      (node (ref "POWER-D2") (pin "A") (pinfunction "A_A") (pintype "passive"))
      (node (ref "U/C-POWER") (pin "1") (pinfunction "S_1") (pintype "passive"))
      (node (ref "U/C-POWER") (pin "4") (pinfunction "S_4") (pintype "passive"))
    )
    (net (code "83") (name "unconnected-(1-8-Pad1)") (class "Default")
      (node (ref "1-8") (pin "1") (pinfunction "1_1") (pintype "passive"))
    )
    (net (code "84") (name "unconnected-(17-24-Pad4)") (class "Default")
      (node (ref "17-24") (pin "4") (pinfunction "4_4") (pintype "passive"))
    )
    (net (code "85") (name "unconnected-(17-24-Pad7)") (class "Default")
      (node (ref "17-24") (pin "7") (pinfunction "7_7") (pintype "passive"))
    )
    (net (code "86") (name "unconnected-(17-24-Pad8)") (class "Default")
      (node (ref "17-24") (pin "8") (pinfunction "8_8") (pintype "passive"))
    )
    (net (code "87") (name "unconnected-(57-64-Pad6)") (class "Default")
      (node (ref "57-64") (pin "6") (pinfunction "6_6") (pintype "passive"))
    )
    (net (code "88") (name "unconnected-(D0-Pad1)") (class "Default")
      (node (ref "D0") (pin "1") (pinfunction "1_1") (pintype "passive"))
    )
    (net (code "89") (name "unconnected-(D0-Pad3)") (class "Default")
      (node (ref "D0") (pin "3") (pinfunction "3_3") (pintype "passive"))
    )
    (net (code "90") (name "unconnected-(D1-Pad1)") (class "Default")
      (node (ref "D1") (pin "1") (pinfunction "1_1") (pintype "passive"))
    )
    (net (code "91") (name "unconnected-(D1-Pad3)") (class "Default")
      (node (ref "D1") (pin "3") (pinfunction "3_3") (pintype "passive"))
    )
    (net (code "92") (name "unconnected-(D2-Pad1)") (class "Default")
      (node (ref "D2") (pin "1") (pinfunction "1_1") (pintype "passive"))
    )
    (net (code "93") (name "unconnected-(D2-Pad3)") (class "Default")
      (node (ref "D2") (pin "3") (pinfunction "3_3") (pintype "passive"))
    )
    (net (code "94") (name "unconnected-(D3-Pad1)") (class "Default")
      (node (ref "D3") (pin "1") (pinfunction "1_1") (pintype "passive"))
    )
    (net (code "95") (name "unconnected-(D3-Pad3)") (class "Default")
      (node (ref "D3") (pin "3") (pinfunction "3_3") (pintype "passive"))
    )
    (net (code "96") (name "unconnected-(K1-Pad1)") (class "Default")
      (node (ref "K1") (pin "1") (pinfunction "1_1") (pintype "passive"))
    )
    (net (code "97") (name "unconnected-(K1-Pad3)") (class "Default")
      (node (ref "K1") (pin "3") (pinfunction "3_3") (pintype "passive"))
    )
    (net (code "98") (name "unconnected-(LCD*-Pad7)") (class "Default")
      (node (ref "LCD*") (pin "7") (pinfunction "7_7") (pintype "passive"))
    )
    (net (code "99") (name "unconnected-(LCD*-Pad8)") (class "Default")
      (node (ref "LCD*") (pin "8") (pinfunction "8_8") (pintype "passive"))
    )
    (net (code "100") (name "unconnected-(LCD-Pad1)") (class "Default")
      (node (ref "LCD") (pin "1") (pinfunction "1_1") (pintype "passive"))
    )
    (net (code "101") (name "unconnected-(LCD-Pad2)") (class "Default")
      (node (ref "LCD") (pin "2") (pinfunction "2_2") (pintype "passive"))
    )
    (net (code "102") (name "unconnected-(MOTOR-POWERA-O-Pad3)") (class "Default")
      (node (ref "MOTOR-POWER") (pin "3") (pinfunction "O_3") (pintype "passive"))
    )
    (net (code "103") (name "unconnected-(MOTOR-POWERB-O-Pad6)") (class "Default")
      (node (ref "MOTOR-POWER") (pin "6") (pinfunction "O_6") (pintype "passive"))
    )
    (net (code "104") (name "unconnected-(PS2-Pad3)") (class "Default")
      (node (ref "PS2") (pin "3") (pinfunction "3_3") (pintype "passive"))
    )
    (net (code "105") (name "unconnected-(PS2-Pad8)") (class "Default")
      (node (ref "PS2") (pin "8") (pinfunction "8_8") (pintype "passive"))
    )
    (net (code "106") (name "unconnected-(PS2-Pad9)") (class "Default")
      (node (ref "PS2") (pin "9") (pinfunction "9_9") (pintype "passive"))
    )
    (net (code "107") (name "unconnected-(U/C-POWERA-O-Pad3)") (class "Default")
      (node (ref "U/C-POWER") (pin "3") (pinfunction "O_3") (pintype "passive"))
    )
    (net (code "108") (name "unconnected-(U/C-POWERB-O-Pad6)") (class "Default")
      (node (ref "U/C-POWER") (pin "6") (pinfunction "O_6") (pintype "passive"))
    )
  )
)
